# POWER.net
KiCad netlist of a schematic drawn in Altium Designer
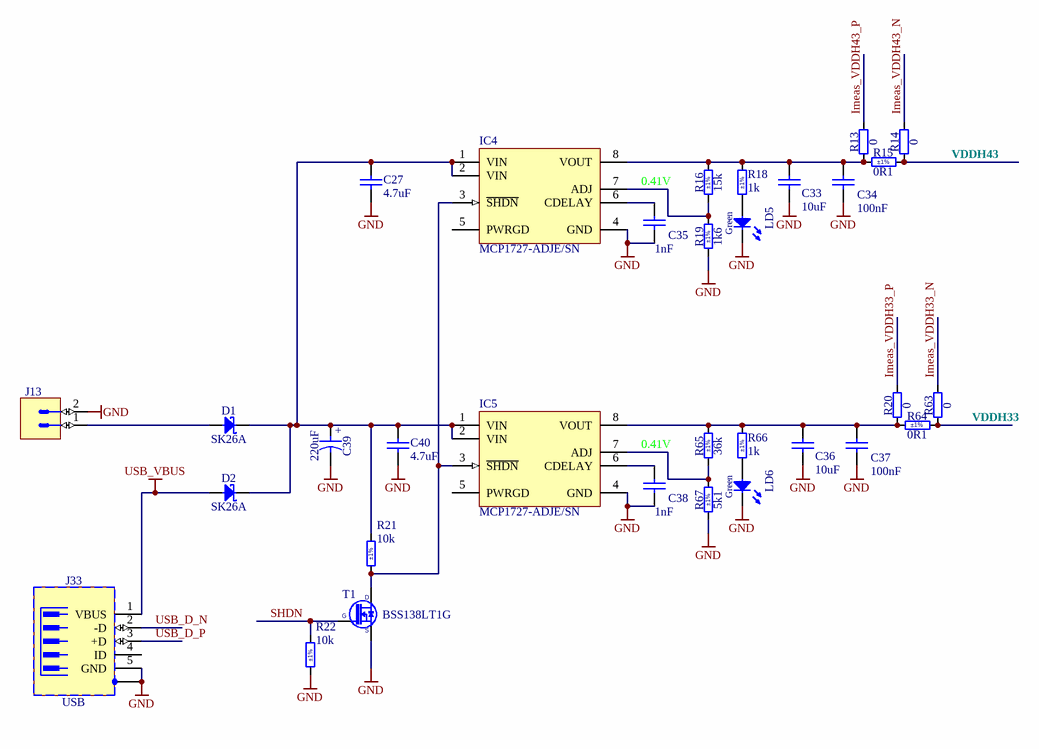
[diagram p0: POWER.SchDoc]

(export (version "E")
  (design (tool "Eeschema 10.0.6"))
  (components
    (comp (ref "C27")
      (value "4.7uF")
      (footprint "CAPC1005X55N")
      (description "Non-polarised capacitor")
      (fields
        (field (name "PART NUMBER") "CC0402_4.7UF_10V_10%_X5R")
        (field (name "VOLTAGE") "10V")
        (field (name "AUTHOR") "CERN DEM BC")
      )
      (libsource (lib "Capacitors") (part "Capacitor - non polarized"))
    )
    (comp (ref "C33")
      (value "10uF")
      (footprint "CAPC1608X80N")
      (description "Non-polarised capacitor")
      (fields
        (field (name "PART NUMBER") "CC0603_10UF_10V_10%_X5R")
        (field (name "VOLTAGE") "10V")
        (field (name "AUTHOR") "CERN DEM JLC")
      )
      (libsource (lib "Capacitors") (part "Capacitor - non polarized"))
    )
    (comp (ref "C34")
      (value "100nF")
      (footprint "CAPC1005X55N")
      (description "Non-polarised capacitor")
      (fields
        (field (name "PART NUMBER") "CC0402_100NF_16V_10%_X5R")
        (field (name "VOLTAGE") "16V")
        (field (name "AUTHOR") "CERN DEM JLC")
      )
      (libsource (lib "Capacitors") (part "Capacitor - non polarized"))
    )
    (comp (ref "C35")
      (value "1nF")
      (footprint "CAPC1005X55N")
      (description "Non-polarised capacitor")
      (fields
        (field (name "PART NUMBER") "CC0402_1NF_50V_5%_C0G")
        (field (name "VOLTAGE") "50V")
        (field (name "AUTHOR") "CERN DEM BC")
      )
      (libsource (lib "Capacitors") (part "Capacitor - non polarized"))
    )
    (comp (ref "C36")
      (value "10uF")
      (footprint "CAPC1608X80N")
      (description "Non-polarised capacitor")
      (fields
        (field (name "PART NUMBER") "CC0603_10UF_10V_10%_X5R")
        (field (name "VOLTAGE") "10V")
        (field (name "AUTHOR") "CERN DEM JLC")
      )
      (libsource (lib "Capacitors") (part "Capacitor - non polarized"))
    )
    (comp (ref "C37")
      (value "100nF")
      (footprint "CAPC1005X55N")
      (description "Non-polarised capacitor")
      (fields
        (field (name "PART NUMBER") "CC0402_100NF_16V_10%_X5R")
        (field (name "VOLTAGE") "16V")
        (field (name "AUTHOR") "CERN DEM JLC")
      )
      (libsource (lib "Capacitors") (part "Capacitor - non polarized"))
    )
    (comp (ref "C38")
      (value "1nF")
      (footprint "CAPC1005X55N")
      (description "Non-polarised capacitor")
      (fields
        (field (name "PART NUMBER") "CC0402_1NF_50V_5%_C0G")
        (field (name "VOLTAGE") "50V")
        (field (name "AUTHOR") "CERN DEM BC")
      )
      (libsource (lib "Capacitors") (part "Capacitor - non polarized"))
    )
    (comp (ref "C39")
      (value "220uF")
      (footprint "CAPMP7343X430N")
      (description "Polarised capacitor")
      (fields
        (field (name "PART NUMBER") "CTE7343-43_220UF_16V_10%")
        (field (name "VOLTAGE") "16V")
        (field (name "AUTHOR") "CERN DEM JLC")
      )
      (libsource (lib "Capacitors") (part "Capacitor - polarized"))
    )
    (comp (ref "C40")
      (value "4.7uF")
      (footprint "CAPC1005X55N")
      (description "Non-polarised capacitor")
      (fields
        (field (name "PART NUMBER") "CC0402_4.7UF_10V_10%_X5R")
        (field (name "VOLTAGE") "10V")
        (field (name "AUTHOR") "CERN DEM BC")
      )
      (libsource (lib "Capacitors") (part "Capacitor - non polarized"))
    )
    (comp (ref "D1")
      (value "SK26A")
      (footprint "DIOM5126X265N")
      (description "Schottky Diode")
      (fields
        (field (name "VOLTAGE") "60V")
        (field (name "POWER") "2A")
        (field (name "AUTHOR") "CERN DEM JMW")
      )
      (libsource (lib "ICs And Semiconductors") (part "Diode Schottky"))
    )
    (comp (ref "D2")
      (value "SK26A")
      (footprint "DIOM5126X265N")
      (description "Schottky Diode")
      (fields
        (field (name "VOLTAGE") "60V")
        (field (name "POWER") "2A")
        (field (name "AUTHOR") "CERN DEM JMW")
      )
      (libsource (lib "ICs And Semiconductors") (part "Diode Schottky"))
    )
    (comp (ref "IC4")
      (value "MCP1727-ADJE/SN")
      (footprint "SO-8")
      (description "1.5A, Low Voltage, Low Quiescent Current LDO Regulator, 8-Pin SOIC 150mil, Extended Temperature")
      (fields (field (name "PUBLISHER") "Altium Limited"))
      (libsource (lib "CCNV") (part "MCP1727-ADJE/SN"))
    )
    (comp (ref "IC5")
      (value "MCP1727-ADJE/SN")
      (footprint "SO-8")
      (description "1.5A, Low Voltage, Low Quiescent Current LDO Regulator, 8-Pin SOIC 150mil, Extended Temperature")
      (fields (field (name "PUBLISHER") "Altium Limited"))
      (libsource (lib "CCNV") (part "MCP1727-ADJE/SN"))
    )
    (comp (ref "J13")
      (value "~")
      (footprint "PHOENIX_1755736")
      (description "Connector 2 Male")
      (fields
        (field (name "PART NUMBER") "PHOENIX_1755736")
        (field (name "MANUFACTURER") "PHOENIX CONTACT")
        (field (name "AUTHOR") "CERN DEM JLC")
      )
      (libsource (lib "Connectors") (part "Connector 2 Male"))
    )
    (comp (ref "J33")
      (value "USB")
      (footprint "MOLEX_500075-1517")
      (description "5 Pin + 1 Shield USB Receptacle")
      (fields
        (field (name "PART NUMBER") "MOLEX_500075-1517")
        (field (name "MANUFACTURER") "MOLEX")
        (field (name "AUTHOR") "CERN DEM JLC")
      )
      (libsource (lib "Connectors") (part "Connector USB 5 Pin + 1Shield"))
    )
    (comp (ref "LD5")
      (value "Green")
      (footprint "LED_KINGBRIGHT_KP-1608CGCK")
      (description "LED Green 1C 2A")
      (fields
        (field (name "PART NUMBER") "LED_KINGBRIGHT_KP-1608CGCK")
        (field (name "MANUFACTURER") "KINGBRIGHT")
        (field (name "AUTHOR") "CERN DEM HF")
      )
      (libsource (lib "ICs And Semiconductors") (part "LED Green 1C 2A"))
    )
    (comp (ref "LD6")
      (value "Green")
      (footprint "LED_KINGBRIGHT_KP-1608CGCK")
      (description "LED Green 1C 2A")
      (fields
        (field (name "PART NUMBER") "LED_KINGBRIGHT_KP-1608CGCK")
        (field (name "MANUFACTURER") "KINGBRIGHT")
        (field (name "AUTHOR") "CERN DEM HF")
      )
      (libsource (lib "ICs And Semiconductors") (part "LED Green 1C 2A"))
    )
    (comp (ref "R13")
      (value "0")
      (footprint "RESC1005X40N")
      (description "Resistor")
      (fields
        (field (name "PART NUMBER") "R0402_0R_JUMPER")
        (field (name "MANUFACTURER") "GENERIC")
        (field (name "AUTHOR") "CERN DEM JLC")
      )
      (libsource (lib "Resistors") (part "Resistor"))
    )
    (comp (ref "R14")
      (value "0")
      (footprint "RESC1005X40N")
      (description "Resistor")
      (fields
        (field (name "PART NUMBER") "R0402_0R_JUMPER")
        (field (name "MANUFACTURER") "GENERIC")
        (field (name "AUTHOR") "CERN DEM JLC")
      )
      (libsource (lib "Resistors") (part "Resistor"))
    )
    (comp (ref "R15")
      (value "0R1")
      (footprint "RESC1608X55N")
      (description "Resistor - 1%")
      (fields
        (field (name "TOLERANCE") "±1%")
        (field (name "PART NUMBER") "R0603_0R1_1%_0.1W_200PPM")
        (field (name "POWER") "0.1W")
        (field (name "AUTHOR") "CERN DEM JMW")
      )
      (libsource (lib "Resistors") (part "Resistor - 1%"))
    )
    (comp (ref "R16")
      (value "15k")
      (footprint "RESC1005X40N")
      (description "Resistor - 1%")
      (fields
        (field (name "TOLERANCE") "±1%")
        (field (name "PART NUMBER") "R0402_15K_1%_0.0625W_100PPM")
        (field (name "POWER") "0.0625W")
        (field (name "AUTHOR") "CERN DEM JMW")
      )
      (libsource (lib "Resistors") (part "Resistor - 1%"))
    )
    (comp (ref "R18")
      (value "1k")
      (footprint "RESC1005X40N")
      (description "Resistor - 1%")
      (fields
        (field (name "TOLERANCE") "±1%")
        (field (name "PART NUMBER") "R0402_1K_1%_0.0625W_100PPM")
        (field (name "POWER") "0.0625W")
        (field (name "AUTHOR") "CERN DEM JLC")
      )
      (libsource (lib "Resistors") (part "Resistor - 1%"))
    )
    (comp (ref "R19")
      (value "1k6")
      (footprint "RESC1005X40N")
      (description "Resistor - 1%")
      (fields
        (field (name "TOLERANCE") "±1%")
        (field (name "PART NUMBER") "R0402_1K6_1%_0.0625W_100PPM")
        (field (name "POWER") "0.0625W")
        (field (name "AUTHOR") "CERN DEM JLC")
      )
      (libsource (lib "Resistors") (part "Resistor - 1%"))
    )
    (comp (ref "R20")
      (value "0")
      (footprint "RESC1005X40N")
      (description "Resistor")
      (fields
        (field (name "PART NUMBER") "R0402_0R_JUMPER")
        (field (name "MANUFACTURER") "GENERIC")
        (field (name "AUTHOR") "CERN DEM JLC")
      )
      (libsource (lib "Resistors") (part "Resistor"))
    )
    (comp (ref "R21")
      (value "10k")
      (footprint "RESC1005X40N")
      (description "Resistor - 1%")
      (fields
        (field (name "TOLERANCE") "±1%")
        (field (name "PART NUMBER") "R0402_10K_1%_0.0625W_100PPM")
        (field (name "POWER") "0.0625W")
        (field (name "AUTHOR") "CERN DEM JLC")
      )
      (libsource (lib "Resistors") (part "Resistor - 1%"))
    )
    (comp (ref "R22")
      (value "10k")
      (footprint "RESC1005X40N")
      (description "Resistor - 1%")
      (fields
        (field (name "TOLERANCE") "±1%")
        (field (name "PART NUMBER") "R0402_10K_1%_0.0625W_100PPM")
        (field (name "POWER") "0.0625W")
        (field (name "AUTHOR") "CERN DEM JLC")
      )
      (libsource (lib "Resistors") (part "Resistor - 1%"))
    )
    (comp (ref "R63")
      (value "0")
      (footprint "RESC1005X40N")
      (description "Resistor")
      (fields
        (field (name "PART NUMBER") "R0402_0R_JUMPER")
        (field (name "MANUFACTURER") "GENERIC")
        (field (name "AUTHOR") "CERN DEM JLC")
      )
      (libsource (lib "Resistors") (part "Resistor"))
    )
    (comp (ref "R64")
      (value "0R1")
      (footprint "RESC1608X55N")
      (description "Resistor - 1%")
      (fields
        (field (name "TOLERANCE") "±1%")
        (field (name "PART NUMBER") "R0603_0R1_1%_0.1W_200PPM")
        (field (name "POWER") "0.1W")
        (field (name "AUTHOR") "CERN DEM JMW")
      )
      (libsource (lib "Resistors") (part "Resistor - 1%"))
    )
    (comp (ref "R65")
      (value "36k")
      (footprint "RESC1005X40N")
      (description "Resistor - 1%")
      (fields
        (field (name "TOLERANCE") "±1%")
        (field (name "PART NUMBER") "R0402_36K_1%_0.0625W_100PPM")
        (field (name "POWER") "0.0625W")
        (field (name "AUTHOR") "CERN DEM JLC")
      )
      (libsource (lib "Resistors") (part "Resistor - 1%"))
    )
    (comp (ref "R66")
      (value "1k")
      (footprint "RESC1005X40N")
      (description "Resistor - 1%")
      (fields
        (field (name "TOLERANCE") "±1%")
        (field (name "PART NUMBER") "R0402_1K_1%_0.0625W_100PPM")
        (field (name "POWER") "0.0625W")
        (field (name "AUTHOR") "CERN DEM JLC")
      )
      (libsource (lib "Resistors") (part "Resistor - 1%"))
    )
    (comp (ref "R67")
      (value "5k1")
      (footprint "RESC1005X40N")
      (description "Resistor - 1%")
      (fields
        (field (name "TOLERANCE") "±1%")
        (field (name "PART NUMBER") "R0402_5K1_1%_0.0625W_100PPM")
        (field (name "POWER") "0.0625W")
        (field (name "AUTHOR") "CERN DEM JLC")
      )
      (libsource (lib "Resistors") (part "Resistor - 1%"))
    )
    (comp (ref "T1")
      (value "BSS138LT1G")
      (footprint "SOT95P240X110-3N")
      (description "N-CHANNEL MOSFET WITH DIODE")
      (fields (field (name "MANUFACTURER") "ON SEMICONDUCTOR") (field (name "AUTHOR") "CERN DEM JLC"))
      (libsource (lib "ICs And Semiconductors") (part "N-MOSFET-D 1G 2S 3D"))
    )
  )
  (nets
    (net (code "1") (name "/Imeas_VDDH33_N") (class "Default")
      (node (ref "R63") (pin "2") (pinfunction "2_2") (pintype "passive"))
    )
    (net (code "2") (name "/Imeas_VDDH33_P") (class "Default")
      (node (ref "R20") (pin "2") (pinfunction "2_2") (pintype "passive"))
    )
    (net (code "3") (name "/Imeas_VDDH43_N") (class "Default")
      (node (ref "R14") (pin "2") (pinfunction "2_2") (pintype "passive"))
    )
    (net (code "4") (name "/Imeas_VDDH43_P") (class "Default")
      (node (ref "R13") (pin "2") (pinfunction "2_2") (pintype "passive"))
    )
    (net (code "5") (name "/SHDN") (class "Default")
      (node (ref "R22") (pin "1") (pinfunction "1_1") (pintype "passive"))
      (node (ref "T1") (pin "1") (pinfunction "G_1") (pintype "passive"))
    )
    (net (code "6") (name "/USB_D_N") (class "Default")
      (node (ref "J33") (pin "2") (pinfunction "-D_2") (pintype "bidirectional"))
    )
    (net (code "7") (name "/USB_D_P") (class "Default")
      (node (ref "J33") (pin "3") (pinfunction "+D_3") (pintype "bidirectional"))
    )
    (net (code "8") (name "/VDDH33") (class "Default")
      (node (ref "R63") (pin "1") (pinfunction "1_1") (pintype "passive"))
      (node (ref "R64") (pin "2") (pinfunction "2_2") (pintype "passive"))
    )
    (net (code "9") (name "/VDDH43") (class "Default")
      (node (ref "R14") (pin "1") (pinfunction "1_1") (pintype "passive"))
      (node (ref "R15") (pin "2") (pinfunction "2_2") (pintype "passive"))
    )
    (net (code "10") (name "GND") (class "Default")
      (node (ref "C27") (pin "1") (pinfunction "1_1") (pintype "passive"))
      (node (ref "C33") (pin "1") (pinfunction "1_1") (pintype "passive"))
      (node (ref "C34") (pin "1") (pinfunction "1_1") (pintype "passive"))
      (node (ref "C35") (pin "1") (pinfunction "1_1") (pintype "passive"))
      (node (ref "C36") (pin "1") (pinfunction "1_1") (pintype "passive"))
      (node (ref "C37") (pin "1") (pinfunction "1_1") (pintype "passive"))
      (node (ref "C38") (pin "1") (pinfunction "1_1") (pintype "passive"))
      (node (ref "C39") (pin "2") (pinfunction "2_2") (pintype "passive"))
      (node (ref "C40") (pin "1") (pinfunction "1_1") (pintype "passive"))
      (node (ref "IC4") (pin "4") (pinfunction "GND_4") (pintype "power_in"))
      (node (ref "IC5") (pin "4") (pinfunction "GND_4") (pintype "power_in"))
      (node (ref "J13") (pin "2") (pinfunction "2_2") (pintype "bidirectional"))
      (node (ref "J33") (pin "5") (pinfunction "GND_5") (pintype "power_in"))
      (node (ref "J33") (pin "6") (pinfunction "SH_6") (pintype "power_in"))
      (node (ref "LD5") (pin "1") (pinfunction "C_1") (pintype "passive"))
      (node (ref "LD6") (pin "1") (pinfunction "C_1") (pintype "passive"))
      (node (ref "R19") (pin "1") (pinfunction "1_1") (pintype "passive"))
      (node (ref "R22") (pin "2") (pinfunction "2_2") (pintype "passive"))
      (node (ref "R67") (pin "1") (pinfunction "1_1") (pintype "passive"))
      (node (ref "T1") (pin "2") (pinfunction "S_2") (pintype "passive"))
    )
    (net (code "11") (name "Net-(D1-A)") (class "Default")
      (node (ref "D1") (pin "2") (pinfunction "A_2") (pintype "passive"))
      (node (ref "J13") (pin "1") (pinfunction "1_1") (pintype "bidirectional"))
    )
    (net (code "12") (name "Net-(D1-C)") (class "Default")
      (node (ref "C27") (pin "2") (pinfunction "2_2") (pintype "passive"))
      (node (ref "C39") (pin "1") (pinfunction "1_1") (pintype "passive"))
      (node (ref "C40") (pin "2") (pinfunction "2_2") (pintype "passive"))
      (node (ref "D1") (pin "1") (pinfunction "C_1") (pintype "passive"))
      (node (ref "D2") (pin "1") (pinfunction "C_1") (pintype "passive"))
      (node (ref "IC4") (pin "1") (pinfunction "VIN_1") (pintype "power_in"))
      (node (ref "IC4") (pin "2") (pinfunction "VIN_2") (pintype "power_in"))
      (node (ref "IC5") (pin "1") (pinfunction "VIN_1") (pintype "power_in"))
      (node (ref "IC5") (pin "2") (pinfunction "VIN_2") (pintype "power_in"))
      (node (ref "R21") (pin "1") (pinfunction "1_1") (pintype "passive"))
    )
    (net (code "13") (name "Net-(IC4-ADJ)") (class "Default")
      (node (ref "IC4") (pin "7") (pinfunction "ADJ_7") (pintype "passive"))
      (node (ref "R16") (pin "1") (pinfunction "1_1") (pintype "passive"))
      (node (ref "R19") (pin "2") (pinfunction "2_2") (pintype "passive"))
    )
    (net (code "14") (name "Net-(IC4-CDELAY)") (class "Default")
      (node (ref "C35") (pin "2") (pinfunction "2_2") (pintype "passive"))
      (node (ref "IC4") (pin "6") (pinfunction "CDELAY_6") (pintype "passive"))
    )
    (net (code "15") (name "Net-(IC4-VOUT)") (class "Default")
      (node (ref "C33") (pin "2") (pinfunction "2_2") (pintype "passive"))
      (node (ref "C34") (pin "2") (pinfunction "2_2") (pintype "passive"))
      (node (ref "IC4") (pin "8") (pinfunction "VOUT_8") (pintype "power_in"))
      (node (ref "R13") (pin "1") (pinfunction "1_1") (pintype "passive"))
      (node (ref "R15") (pin "1") (pinfunction "1_1") (pintype "passive"))
      (node (ref "R16") (pin "2") (pinfunction "2_2") (pintype "passive"))
      (node (ref "R18") (pin "2") (pinfunction "2_2") (pintype "passive"))
    )
    (net (code "16") (name "Net-(IC4-~{SHDN})") (class "Default")
      (node (ref "IC4") (pin "3") (pinfunction "~{SHDN}_3") (pintype "input"))
      (node (ref "IC5") (pin "3") (pinfunction "~{SHDN}_3") (pintype "input"))
      (node (ref "R21") (pin "2") (pinfunction "2_2") (pintype "passive"))
      (node (ref "T1") (pin "3") (pinfunction "D_3") (pintype "passive"))
    )
    (net (code "17") (name "Net-(IC5-ADJ)") (class "Default")
      (node (ref "IC5") (pin "7") (pinfunction "ADJ_7") (pintype "passive"))
      (node (ref "R65") (pin "1") (pinfunction "1_1") (pintype "passive"))
      (node (ref "R67") (pin "2") (pinfunction "2_2") (pintype "passive"))
    )
    (net (code "18") (name "Net-(IC5-CDELAY)") (class "Default")
      (node (ref "C38") (pin "2") (pinfunction "2_2") (pintype "passive"))
      (node (ref "IC5") (pin "6") (pinfunction "CDELAY_6") (pintype "passive"))
    )
    (net (code "19") (name "Net-(IC5-VOUT)") (class "Default")
      (node (ref "C36") (pin "2") (pinfunction "2_2") (pintype "passive"))
      (node (ref "C37") (pin "2") (pinfunction "2_2") (pintype "passive"))
      (node (ref "IC5") (pin "8") (pinfunction "VOUT_8") (pintype "power_in"))
      (node (ref "R20") (pin "1") (pinfunction "1_1") (pintype "passive"))
      (node (ref "R64") (pin "1") (pinfunction "1_1") (pintype "passive"))
      (node (ref "R65") (pin "2") (pinfunction "2_2") (pintype "passive"))
      (node (ref "R66") (pin "2") (pinfunction "2_2") (pintype "passive"))
    )
    (net (code "20") (name "Net-(LD5-A)") (class "Default")
      (node (ref "LD5") (pin "2") (pinfunction "A_2") (pintype "passive"))
      (node (ref "R18") (pin "1") (pinfunction "1_1") (pintype "passive"))
    )
    (net (code "21") (name "Net-(LD6-A)") (class "Default")
      (node (ref "LD6") (pin "2") (pinfunction "A_2") (pintype "passive"))
      (node (ref "R66") (pin "1") (pinfunction "1_1") (pintype "passive"))
    )
    (net (code "22") (name "USB_VBUS") (class "Default")
      (node (ref "D2") (pin "2") (pinfunction "A_2") (pintype "passive"))
      (node (ref "J33") (pin "1") (pinfunction "VBUS_1") (pintype "power_in"))
    )
    (net (code "23") (name "unconnected-(IC4-PWRGD-Pad5)") (class "Default")
      (node (ref "IC4") (pin "5") (pinfunction "PWRGD_5") (pintype "power_in"))
    )
    (net (code "24") (name "unconnected-(IC5-PWRGD-Pad5)") (class "Default")
      (node (ref "IC5") (pin "5") (pinfunction "PWRGD_5") (pintype "power_in"))
    )
    (net (code "25") (name "unconnected-(J33-ID-Pad4)") (class "Default")
      (node (ref "J33") (pin "4") (pinfunction "ID_4") (pintype "passive"))
    )
  )
)
